# ui.net
KiCad netlist of a schematic drawn in Altium Designer
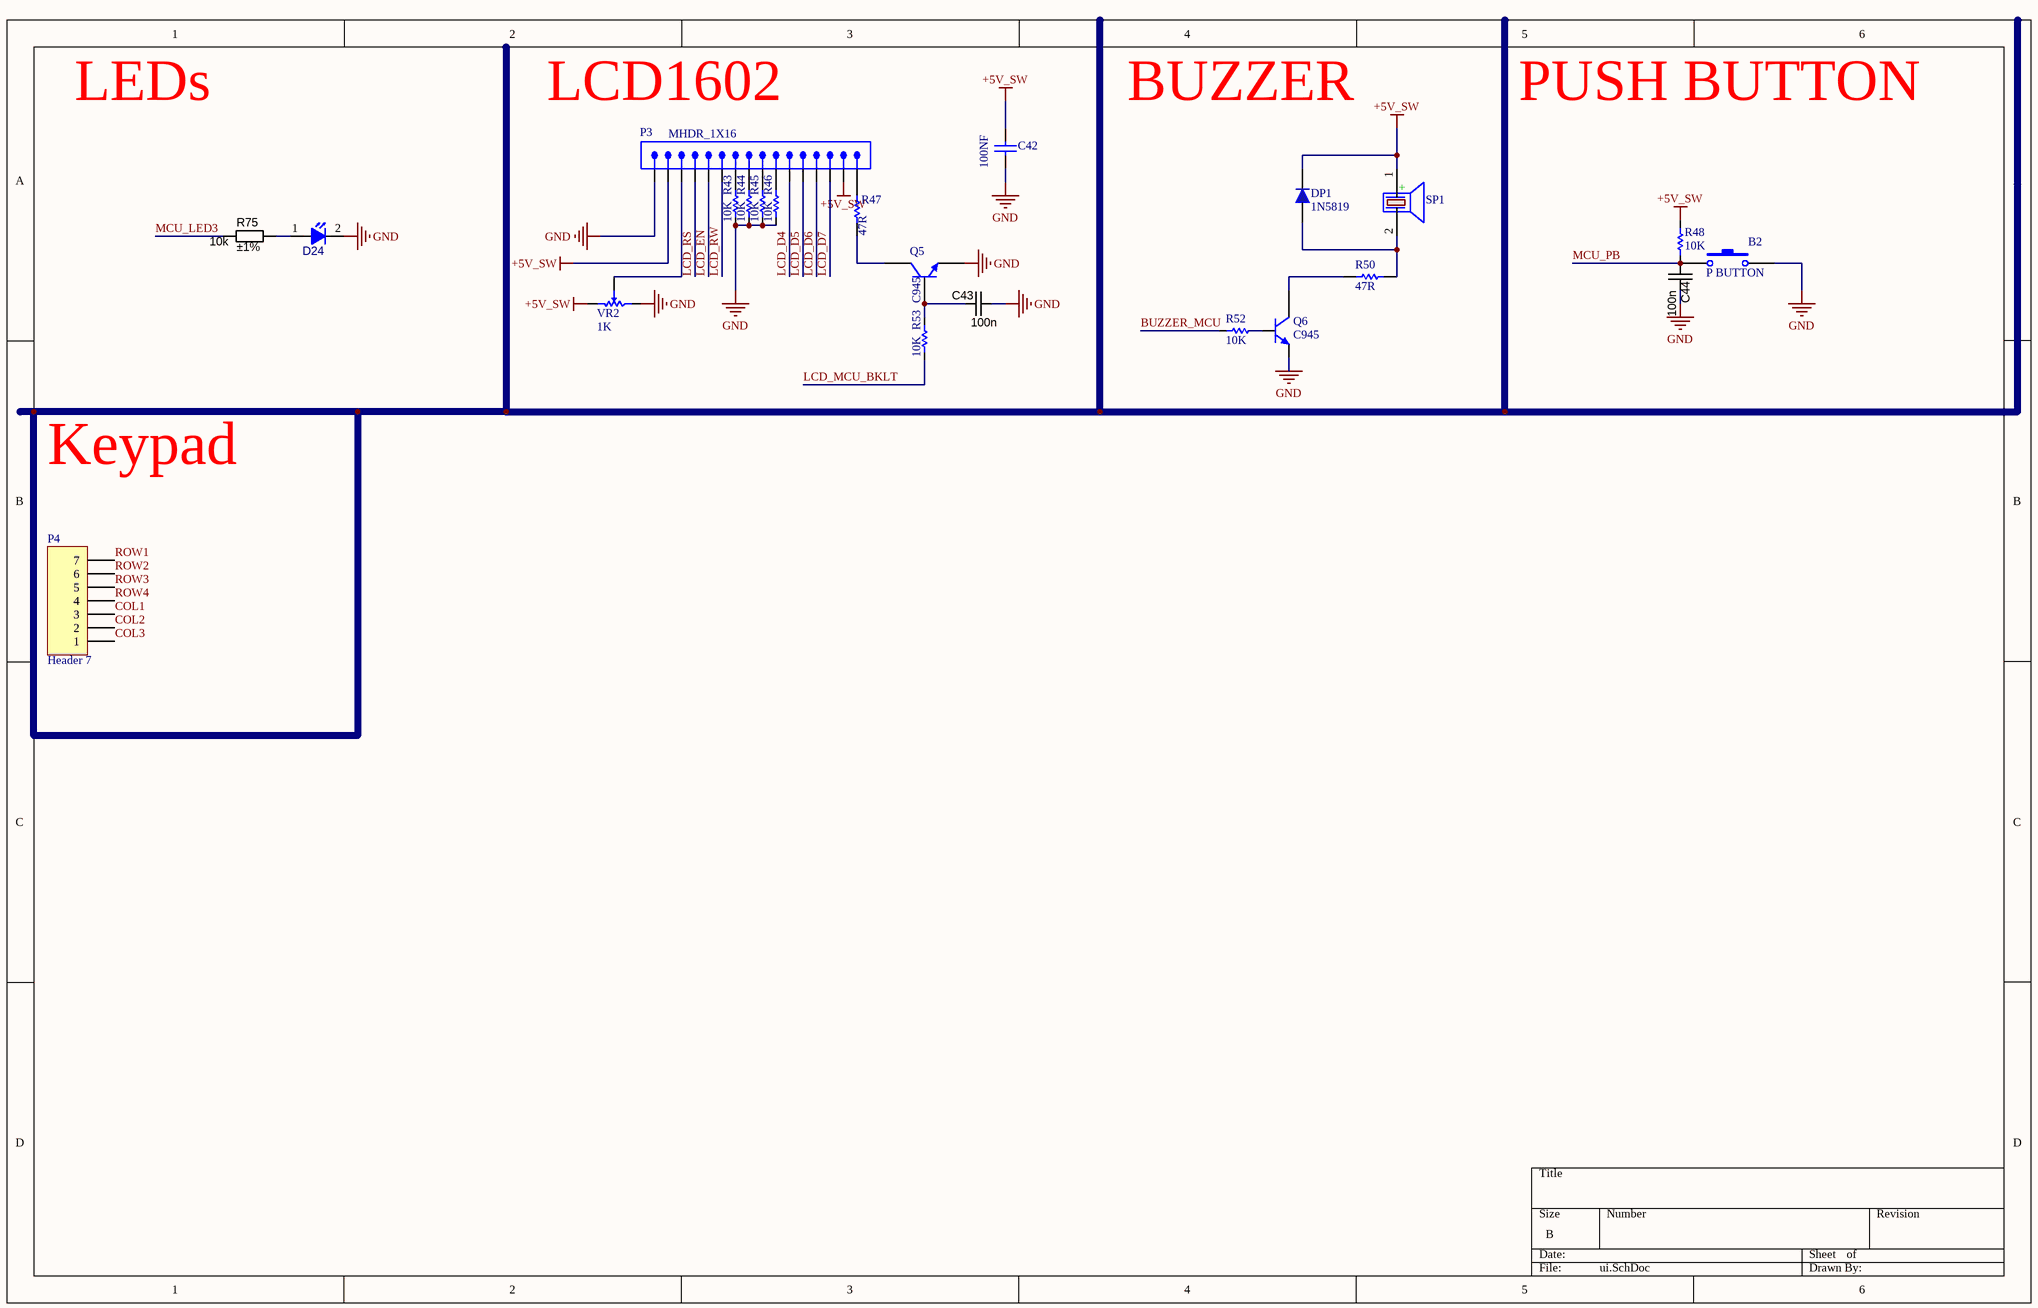
[diagram p0: ui.SchDoc]

(export (version "E")
  (design (tool "Eeschema 10.0.6"))
  (components
    (comp (ref "B2")
      (value "P BUTTON")
      (footprint "MY_SPST-0.5")
      (libsource (lib "AMINLIB") (part "PUSH BUTTON_SMALL"))
    )
    (comp (ref "C42")
      (value "100NF")
      (footprint "CAP0603")
      (description "TOTAL CAPACITOR SMD PACK")
      (fields (field (name "DESIGNER") "Abbas Basereh"))
      (libsource (lib "Altium") (part "CAP SMD PACKAGE"))
    )
    (comp (ref "C43")
      (value "100n")
      (footprint "CAPC2012X135N")
      (description "Capacitor SMD Cer 100nF 10% 50V X7R 0805")
      (fields (field (name "TOLERANCE") "±10%") (field (name "Comment") "approved sub OK"))
      (libsource (lib "Utiliti_Library") (part "CAPC_100n_0805_X7R_50V_10%"))
    )
    (comp (ref "C44")
      (value "100n")
      (footprint "CAPC2012X135N")
      (description "Capacitor SMD Cer 100nF 10% 50V X7R 0805")
      (fields (field (name "TOLERANCE") "±10%") (field (name "Comment") "approved sub OK"))
      (libsource (lib "Utiliti_Library") (part "CAPC_100n_0805_X7R_50V_10%"))
    )
    (comp (ref "D24")
      (value "LED SMD 0603")
      (footprint "LED SMD 0603 2 (Green)")
      (libsource (lib "LED") (part "LED SMD 0603"))
    )
    (comp (ref "DP1")
      (value "1N5819")
      (footprint "430X270D")
      (description "Schottkey Rectifiers")
      (fields (field (name "DESIGNER") "Abbas Basereh"))
      (libsource (lib "2017AbbasBasereh9365731239 -ver1") (part "1N5819"))
    )
    (comp (ref "P3")
      (value "MHDR_1X16")
      (footprint "MHDR1X16-254P")
      (description "Male Header 1X16")
      (libsource (lib "altium-import") (part "root_1_MHDR_1X16_"))
    )
    (comp (ref "P4")
      (value "Header 7")
      (footprint "HDR1X7")
      (description "Header, 7-Pin")
      (fields (field (name "PUBLISHER") "Altium Limited"))
      (libsource (lib "altium-import") (part "root_2_Header 7_"))
    )
    (comp (ref "Q5")
      (value "C945")
      (footprint "SOT23_N")
      (description "NPN Silicon Epitaxial Planar Transistor")
      (fields (field (name "PUBLISHER") "Abbas Basereh"))
      (libsource (lib "2017AbbasBasereh9365731239 -ver1") (part "C945"))
    )
    (comp (ref "Q6")
      (value "C945")
      (footprint "SOT23_N")
      (description "NPN Silicon Epitaxial Planar Transistor")
      (fields (field (name "PUBLISHER") "Abbas Basereh"))
      (libsource (lib "2017AbbasBasereh9365731239 -ver1") (part "C945"))
    )
    (comp (ref "R43")
      (value "10K")
      (footprint "RES 0603 (1608X06L)")
      (description "Resistor")
      (fields (field (name "TOLERANCE") "5%") (field (name "POWER") "1/4 W"))
      (libsource (lib "altium-import") (part "root_1_Resistor_"))
    )
    (comp (ref "R44")
      (value "10K")
      (footprint "RES 0603 (1608X06L)")
      (description "Resistor")
      (fields (field (name "TOLERANCE") "5%") (field (name "POWER") "1/4 W"))
      (libsource (lib "altium-import") (part "root_1_Resistor_"))
    )
    (comp (ref "R45")
      (value "10K")
      (footprint "RES 0603 (1608X06L)")
      (description "Resistor")
      (fields (field (name "TOLERANCE") "5%") (field (name "POWER") "1/4 W"))
      (libsource (lib "altium-import") (part "root_1_Resistor_"))
    )
    (comp (ref "R46")
      (value "10K")
      (footprint "RES 0603 (1608X06L)")
      (description "Resistor")
      (fields (field (name "TOLERANCE") "5%") (field (name "POWER") "1/4 W"))
      (libsource (lib "altium-import") (part "root_1_Resistor_"))
    )
    (comp (ref "R47")
      (value "47R")
      (footprint "RES1206")
      (description "TOTAL SMD RESISTOR PACK")
      (fields (field (name "DESIGNER") "Abbas Basereh"))
      (libsource (lib "2017AbbasBasereh9365731239 -ver1") (part "RES SMD PACKAGE"))
    )
    (comp (ref "R48")
      (value "10K")
      (footprint "RES 0603 (1608X06L)")
      (description "Resistor")
      (fields (field (name "TOLERANCE") "5%") (field (name "POWER") "1/4 W"))
      (libsource (lib "altium-import") (part "root_3_Resistor_"))
    )
    (comp (ref "R50")
      (value "47R")
      (footprint "RES1206")
      (description "TOTAL SMD RESISTOR PACK")
      (fields (field (name "DESIGNER") "Abbas Basereh"))
      (libsource (lib "2017AbbasBasereh9365731239 -ver1") (part "RES SMD PACKAGE"))
    )
    (comp (ref "R52")
      (value "10K")
      (footprint "RES 0603 (1608X06L)")
      (description "Resistor")
      (fields (field (name "TOLERANCE") "5%") (field (name "POWER") "1/4 W"))
      (libsource (lib "altium-import") (part "root_0_Resistor_"))
    )
    (comp (ref "R53")
      (value "10K")
      (footprint "RES 0603 (1608X06L)")
      (description "Resistor")
      (fields (field (name "TOLERANCE") "5%") (field (name "POWER") "1/4 W"))
      (libsource (lib "altium-import") (part "root_1_Resistor_"))
    )
    (comp (ref "R75")
      (value "10k")
      (footprint "RESC1608X55N")
      (description "Resistor SMD chip 1k Ohm 0.1W 1% 0603")
      (fields (field (name "TOLERANCE") "±1%"))
      (libsource (lib "Utiliti_Library") (part "RES_1K_0603_1%"))
    )
    (comp (ref "SP1")
      (value "~")
      (footprint "BUZZER 7.62mm DC")
      (description "PIEZO BUZZER ACTIVE")
      (fields (field (name "DESIGNER") "Abbas Basereh") (field (name "PUBLISHER") "Abbas Basereh"))
      (libsource (lib "2017AbbasBasereh9365731239 -ver1") (part "PIEZO BUZZER"))
    )
    (comp (ref "VR2")
      (value "1K")
      (footprint "Multi Turn")
      (description "Multi Turn")
      (fields
        (field (name "PUBLISHER") "Seyed Razi vesali (SRV)")
        (field (name "EMAIL") "Razi.vesali@gmail.com")
      )
      (libsource (lib "resistors") (part "Multi Turn"))
    )
  )
  (nets
    (net (code "1") (name "+5V_SW") (class "Default")
      (node (ref "C42") (pin "2") (pinfunction "2_2") (pintype "passive"))
      (node (ref "DP1") (pin "2") (pintype "passive"))
      (node (ref "P3") (pin "15") (pinfunction "15_15") (pintype "passive"))
      (node (ref "P3") (pin "2") (pinfunction "2_2") (pintype "passive"))
      (node (ref "R48") (pin "1") (pinfunction "1_1") (pintype "passive"))
      (node (ref "SP1") (pin "1") (pinfunction "+_1") (pintype "passive"))
      (node (ref "VR2") (pin "2") (pinfunction "CW_2") (pintype "passive"))
    )
    (net (code "2") (name "/BUZZER_MCU") (class "Default")
      (node (ref "R52") (pin "1") (pinfunction "1_1") (pintype "passive"))
    )
    (net (code "3") (name "/COL1") (class "Default")
      (node (ref "P4") (pin "3") (pinfunction "3_3") (pintype "passive"))
    )
    (net (code "4") (name "/COL2") (class "Default")
      (node (ref "P4") (pin "2") (pinfunction "2_2") (pintype "passive"))
    )
    (net (code "5") (name "/COL3") (class "Default")
      (node (ref "P4") (pin "1") (pinfunction "1_1") (pintype "passive"))
    )
    (net (code "6") (name "/LCD_D4") (class "Default")
      (node (ref "P3") (pin "11") (pinfunction "11_11") (pintype "passive"))
    )
    (net (code "7") (name "/LCD_D5") (class "Default")
      (node (ref "P3") (pin "12") (pinfunction "12_12") (pintype "passive"))
    )
    (net (code "8") (name "/LCD_D6") (class "Default")
      (node (ref "P3") (pin "13") (pinfunction "13_13") (pintype "passive"))
    )
    (net (code "9") (name "/LCD_D7") (class "Default")
      (node (ref "P3") (pin "14") (pinfunction "14_14") (pintype "passive"))
    )
    (net (code "10") (name "/LCD_EN") (class "Default")
      (node (ref "P3") (pin "5") (pinfunction "5_5") (pintype "passive"))
    )
    (net (code "11") (name "/LCD_MCU_BKLT") (class "Default")
      (node (ref "R53") (pin "1") (pinfunction "1_1") (pintype "passive"))
    )
    (net (code "12") (name "/LCD_RS") (class "Default")
      (node (ref "P3") (pin "4") (pinfunction "4_4") (pintype "passive"))
    )
    (net (code "13") (name "/LCD_RW") (class "Default")
      (node (ref "P3") (pin "6") (pinfunction "6_6") (pintype "passive"))
    )
    (net (code "14") (name "/MCU_LED3") (class "Default")
      (node (ref "R75") (pin "1") (pinfunction "1_1") (pintype "passive"))
    )
    (net (code "15") (name "/MCU_PB") (class "Default")
      (node (ref "B2") (pin "1") (pinfunction "1_1") (pintype "passive"))
      (node (ref "C44") (pin "2") (pintype "passive"))
      (node (ref "R48") (pin "2") (pinfunction "2_2") (pintype "passive"))
    )
    (net (code "16") (name "/ROW1") (class "Default")
      (node (ref "P4") (pin "7") (pinfunction "7_7") (pintype "passive"))
    )
    (net (code "17") (name "/ROW2") (class "Default")
      (node (ref "P4") (pin "6") (pinfunction "6_6") (pintype "passive"))
    )
    (net (code "18") (name "/ROW3") (class "Default")
      (node (ref "P4") (pin "5") (pinfunction "5_5") (pintype "passive"))
    )
    (net (code "19") (name "/ROW4") (class "Default")
      (node (ref "P4") (pin "4") (pinfunction "4_4") (pintype "passive"))
    )
    (net (code "20") (name "GND") (class "Default")
      (node (ref "B2") (pin "2") (pinfunction "2_2") (pintype "passive"))
      (node (ref "C42") (pin "1") (pinfunction "1_1") (pintype "passive"))
      (node (ref "C43") (pin "1") (pintype "passive"))
      (node (ref "C44") (pin "1") (pintype "passive"))
      (node (ref "D24") (pin "2") (pinfunction "CATHODE_2") (pintype "passive"))
      (node (ref "P3") (pin "1") (pinfunction "1_1") (pintype "passive"))
      (node (ref "Q5") (pin "2") (pinfunction "E_2") (pintype "passive"))
      (node (ref "Q6") (pin "2") (pinfunction "E_2") (pintype "passive"))
      (node (ref "R43") (pin "1") (pinfunction "1_1") (pintype "passive"))
      (node (ref "R44") (pin "1") (pinfunction "1_1") (pintype "passive"))
      (node (ref "R45") (pin "1") (pinfunction "1_1") (pintype "passive"))
      (node (ref "R46") (pin "1") (pinfunction "1_1") (pintype "passive"))
      (node (ref "VR2") (pin "1") (pinfunction "CCW_1") (pintype "passive"))
    )
    (net (code "21") (name "Net-(D24-ANODE)") (class "Default")
      (node (ref "D24") (pin "1") (pinfunction "ANODE_1") (pintype "passive"))
      (node (ref "R75") (pin "2") (pinfunction "2_2") (pintype "passive"))
    )
    (net (code "22") (name "Net-(P3-Pad7)") (class "Default")
      (node (ref "P3") (pin "7") (pinfunction "7_7") (pintype "passive"))
      (node (ref "R43") (pin "2") (pinfunction "2_2") (pintype "passive"))
    )
    (net (code "23") (name "Net-(P3-Pad8)") (class "Default")
      (node (ref "P3") (pin "8") (pinfunction "8_8") (pintype "passive"))
      (node (ref "R44") (pin "2") (pinfunction "2_2") (pintype "passive"))
    )
    (net (code "24") (name "Net-(P3-Pad9)") (class "Default")
      (node (ref "P3") (pin "9") (pinfunction "9_9") (pintype "passive"))
      (node (ref "R45") (pin "2") (pinfunction "2_2") (pintype "passive"))
    )
    (net (code "25") (name "Net-(P3-Pad10)") (class "Default")
      (node (ref "P3") (pin "10") (pinfunction "10_10") (pintype "passive"))
      (node (ref "R46") (pin "2") (pinfunction "2_2") (pintype "passive"))
    )
    (net (code "26") (name "Net-(P3-Pad16)") (class "Default")
      (node (ref "P3") (pin "16") (pinfunction "16_16") (pintype "passive"))
      (node (ref "R47") (pin "2") (pinfunction "2_2") (pintype "passive"))
    )
    (net (code "27") (name "Net-(Q5-B)") (class "Default")
      (node (ref "C43") (pin "2") (pintype "passive"))
      (node (ref "Q5") (pin "1") (pinfunction "B_1") (pintype "passive"))
      (node (ref "R53") (pin "2") (pinfunction "2_2") (pintype "passive"))
    )
    (net (code "28") (name "Net-(Q5-C)") (class "Default")
      (node (ref "Q5") (pin "3") (pinfunction "C_3") (pintype "passive"))
      (node (ref "R47") (pin "1") (pinfunction "1_1") (pintype "passive"))
    )
    (net (code "29") (name "Net-(Q6-B)") (class "Default")
      (node (ref "Q6") (pin "1") (pinfunction "B_1") (pintype "passive"))
      (node (ref "R52") (pin "2") (pinfunction "2_2") (pintype "passive"))
    )
    (net (code "30") (name "Net-(Q6-C)") (class "Default")
      (node (ref "Q6") (pin "3") (pinfunction "C_3") (pintype "passive"))
      (node (ref "R50") (pin "1") (pinfunction "1_1") (pintype "passive"))
    )
    (net (code "31") (name "Net-(SP1--)") (class "Default")
      (node (ref "DP1") (pin "1") (pintype "passive"))
      (node (ref "R50") (pin "2") (pinfunction "2_2") (pintype "passive"))
      (node (ref "SP1") (pin "2") (pinfunction "-_2") (pintype "passive"))
    )
    (net (code "32") (name "Net-(VR2-Setpoint)") (class "Default")
      (node (ref "P3") (pin "3") (pinfunction "3_3") (pintype "passive"))
      (node (ref "VR2") (pin "3") (pinfunction "Setpoint_3") (pintype "passive"))
    )
  )
)
